# GPS.net
KiCad netlist of a schematic drawn in Altium Designer
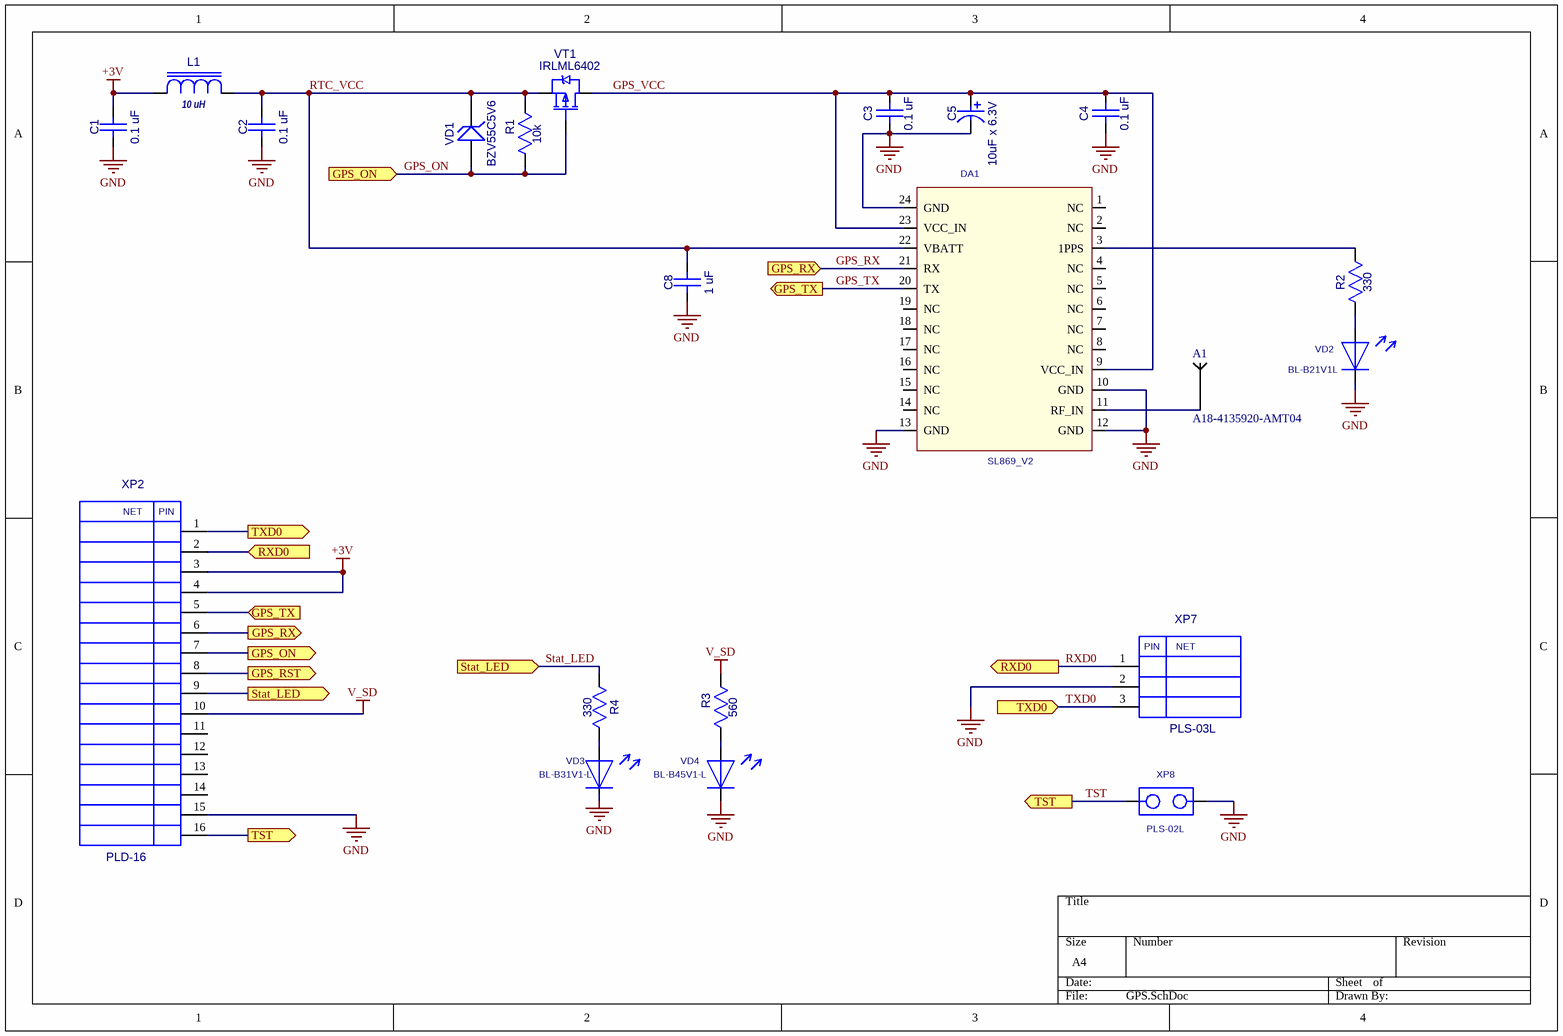
[diagram p0: GPS.SchDoc]

(export (version "E")
  (design (tool "Eeschema 10.0.6"))
  (components
    (comp (ref "A1")
      (value "A18-4135920-AMT04")
      (footprint "BY-GPS-204")
      (description "Passive GPS Antenna")
      (libsource (lib "gprs_modem_2") (part "BY-GPS-204"))
    )
    (comp (ref "C1")
      (value "0.1 uF")
      (footprint "CC0603-3M")
      (description "CC0603")
      (libsource (lib "*") (part "CC0603"))
    )
    (comp (ref "C2")
      (value "0.1 uF")
      (footprint "CC0603-3M")
      (description "CC0603")
      (libsource (lib "*") (part "CC0603"))
    )
    (comp (ref "C3")
      (value "0.1 uF")
      (footprint "CC0603-3M")
      (description "CC0603")
      (libsource (lib "*") (part "CC0603"))
    )
    (comp (ref "C4")
      (value "0.1 uF")
      (footprint "CC0603-3M")
      (description "CC0603")
      (libsource (lib "*") (part "CC0603"))
    )
    (comp (ref "C5")
      (value "10uF x 6.3V")
      (footprint "TAJ-A_M")
      (description "TAJ-A")
      (libsource (lib "gprs_modem") (part "TAJ-A"))
    )
    (comp (ref "C8")
      (value "1 uF")
      (footprint "CC0603-3M")
      (description "CC0603")
      (libsource (lib "*") (part "CC0603"))
    )
    (comp (ref "DA1") (value "SL869_V2") (footprint "SL868") (libsource (lib "gprs_modem") (part "SL869_V2")))
    (comp (ref "L1")
      (value "10 uH")
      (footprint "RC0805-MIDI-2")
      (description "L0805")
      (libsource (lib "*") (part "L0805"))
    )
    (comp (ref "R1")
      (value "10k")
      (footprint "RC0603-3M")
      (description "RC0603")
      (libsource (lib "*") (part "RC0603"))
    )
    (comp (ref "R2")
      (value "330")
      (footprint "RC0603-3M")
      (description "RC0603")
      (libsource (lib "*") (part "RC0603"))
    )
    (comp (ref "R3")
      (value "560")
      (footprint "RC0603-3M")
      (description "RC0603")
      (libsource (lib "*") (part "RC0603"))
    )
    (comp (ref "R4")
      (value "330")
      (footprint "RC0603-3M")
      (description "RC0603")
      (libsource (lib "*") (part "RC0603"))
    )
    (comp (ref "VD1")
      (value "BZV55C5V6")
      (footprint "SOD80")
      (description "Zener Voltage Regulator Diode")
      (libsource (lib "gprs_modem") (part "BZV55C5V1"))
    )
    (comp (ref "VD2")
      (value "BL-B21V1L")
      (footprint "LED3")
      (description "LED_3")
      (libsource (lib "gprs_modem") (part "LED_3"))
    )
    (comp (ref "VD3")
      (value "BL-B31V1-L")
      (footprint "LED3")
      (description "LED_3")
      (libsource (lib "gprs_modem") (part "LED_3"))
    )
    (comp (ref "VD4")
      (value "BL-B45V1-L")
      (footprint "LED3")
      (description "LED_3")
      (libsource (lib "gprs_modem") (part "LED_3"))
    )
    (comp (ref "VT1")
      (value "IRLML6402")
      (footprint "SOT-23(123)")
      (description "HEXFET Power MOSFET")
      (libsource (lib "gprs_modem") (part "IRLML6402"))
    )
    (comp (ref "XP2") (value "PLD-16") (footprint "PIN16") (libsource (lib "gprs_modem") (part "PLD-16")))
    (comp (ref "XP7") (value "PLS-03L") (footprint "PLS-03L") (libsource (lib "gprs_modem") (part "PLS-03L")))
    (comp (ref "XP8") (value "PLS-02L") (footprint "PLS-02L") (libsource (lib "gprs_modem") (part "PLS-02L")))
  )
  (nets
    (net (code "1") (name "+3V") (class "Default")
      (node (ref "C1") (pin "2") (pinfunction "B_2") (pintype "passive"))
      (node (ref "L1") (pin "1") (pinfunction "A_1") (pintype "passive"))
      (node (ref "XP2") (pin "3") (pinfunction "3_3") (pintype "passive"))
      (node (ref "XP2") (pin "4") (pinfunction "4_4") (pintype "passive"))
    )
    (net (code "2") (name "/GPS_ON") (class "Default")
      (node (ref "R1") (pin "2") (pinfunction "B_2") (pintype "passive"))
      (node (ref "VD1") (pin "1") (pinfunction "A_1") (pintype "passive"))
      (node (ref "VT1") (pin "1") (pinfunction "G_1") (pintype "passive"))
      (node (ref "XP2") (pin "7") (pinfunction "7_7") (pintype "passive"))
    )
    (net (code "3") (name "/GPS_RST") (class "Default")
      (node (ref "XP2") (pin "8") (pinfunction "8_8") (pintype "passive"))
    )
    (net (code "4") (name "/GPS_RX") (class "Default")
      (node (ref "DA1") (pin "21") (pinfunction "RX_21") (pintype "passive"))
      (node (ref "XP2") (pin "6") (pinfunction "6_6") (pintype "passive"))
    )
    (net (code "5") (name "/GPS_TX") (class "Default")
      (node (ref "DA1") (pin "20") (pinfunction "TX_20") (pintype "passive"))
      (node (ref "XP2") (pin "5") (pinfunction "5_5") (pintype "passive"))
    )
    (net (code "6") (name "/GPS_VCC") (class "Default")
      (node (ref "C3") (pin "1") (pinfunction "A_1") (pintype "passive"))
      (node (ref "C4") (pin "1") (pinfunction "A_1") (pintype "passive"))
      (node (ref "C5") (pin "1") (pinfunction "A_1") (pintype "passive"))
      (node (ref "DA1") (pin "23") (pinfunction "VCC_IN_23") (pintype "passive"))
      (node (ref "DA1") (pin "9") (pinfunction "VCC_IN_9") (pintype "passive"))
      (node (ref "VT1") (pin "3") (pinfunction "D_3") (pintype "passive"))
    )
    (net (code "7") (name "/RTC_VCC") (class "Default")
      (node (ref "C2") (pin "2") (pinfunction "B_2") (pintype "passive"))
      (node (ref "C8") (pin "2") (pinfunction "B_2") (pintype "passive"))
      (node (ref "DA1") (pin "22") (pinfunction "VBATT_22") (pintype "passive"))
      (node (ref "L1") (pin "2") (pinfunction "B_2") (pintype "passive"))
      (node (ref "R1") (pin "1") (pinfunction "A_1") (pintype "passive"))
      (node (ref "VD1") (pin "2") (pintype "passive"))
      (node (ref "VT1") (pin "2") (pinfunction "S_2") (pintype "passive"))
    )
    (net (code "8") (name "/RXD0") (class "Default")
      (node (ref "XP2") (pin "2") (pinfunction "2_2") (pintype "passive"))
      (node (ref "XP7") (pin "1") (pinfunction "1_1") (pintype "passive"))
    )
    (net (code "9") (name "/Stat_LED") (class "Default")
      (node (ref "R4") (pin "2") (pinfunction "B_2") (pintype "passive"))
      (node (ref "XP2") (pin "9") (pinfunction "9_9") (pintype "passive"))
    )
    (net (code "10") (name "/TST") (class "Default")
      (node (ref "XP2") (pin "16") (pinfunction "16_16") (pintype "passive"))
      (node (ref "XP8") (pin "1") (pintype "passive"))
    )
    (net (code "11") (name "/TXD0") (class "Default")
      (node (ref "XP2") (pin "1") (pinfunction "1_1") (pintype "passive"))
      (node (ref "XP7") (pin "3") (pinfunction "3_3") (pintype "passive"))
    )
    (net (code "12") (name "GND") (class "Default")
      (node (ref "C1") (pin "1") (pinfunction "A_1") (pintype "passive"))
      (node (ref "C2") (pin "1") (pinfunction "A_1") (pintype "passive"))
      (node (ref "C3") (pin "2") (pinfunction "B_2") (pintype "passive"))
      (node (ref "C4") (pin "2") (pinfunction "B_2") (pintype "passive"))
      (node (ref "C5") (pin "2") (pinfunction "B_2") (pintype "passive"))
      (node (ref "C8") (pin "1") (pinfunction "A_1") (pintype "passive"))
      (node (ref "DA1") (pin "10") (pinfunction "GND_10") (pintype "passive"))
      (node (ref "DA1") (pin "12") (pinfunction "GND_12") (pintype "passive"))
      (node (ref "DA1") (pin "13") (pinfunction "GND_13") (pintype "passive"))
      (node (ref "DA1") (pin "24") (pinfunction "GND_24") (pintype "passive"))
      (node (ref "VD2") (pin "1") (pintype "passive"))
      (node (ref "VD3") (pin "1") (pintype "passive"))
      (node (ref "VD4") (pin "1") (pintype "passive"))
      (node (ref "XP2") (pin "15") (pinfunction "15_15") (pintype "passive"))
      (node (ref "XP7") (pin "2") (pinfunction "2_2") (pintype "passive"))
      (node (ref "XP8") (pin "2") (pintype "passive"))
    )
    (net (code "13") (name "Net-(DA1-1PPS)") (class "Default")
      (node (ref "DA1") (pin "3") (pinfunction "1PPS_3") (pintype "passive"))
      (node (ref "R2") (pin "1") (pinfunction "A_1") (pintype "passive"))
    )
    (net (code "14") (name "Net-(DA1-RF_IN)") (class "Default")
      (node (ref "A1") (pin "1") (pinfunction "1_1") (pintype "passive"))
      (node (ref "DA1") (pin "11") (pinfunction "RF_IN_11") (pintype "passive"))
    )
    (net (code "15") (name "Net-(R2-B)") (class "Default")
      (node (ref "R2") (pin "2") (pinfunction "B_2") (pintype "passive"))
      (node (ref "VD2") (pin "2") (pintype "passive"))
    )
    (net (code "16") (name "Net-(R3-A)") (class "Default")
      (node (ref "R3") (pin "1") (pinfunction "A_1") (pintype "passive"))
      (node (ref "VD4") (pin "2") (pintype "passive"))
    )
    (net (code "17") (name "Net-(R4-A)") (class "Default")
      (node (ref "R4") (pin "1") (pinfunction "A_1") (pintype "passive"))
      (node (ref "VD3") (pin "2") (pintype "passive"))
    )
    (net (code "18") (name "V_SD") (class "Default")
      (node (ref "R3") (pin "2") (pinfunction "B_2") (pintype "passive"))
      (node (ref "XP2") (pin "10") (pinfunction "10_10") (pintype "passive"))
    )
    (net (code "19") (name "unconnected-(DA1-NC-Pad1)") (class "Default")
      (node (ref "DA1") (pin "1") (pinfunction "NC_1") (pintype "passive"))
    )
    (net (code "20") (name "unconnected-(DA1-NC-Pad2)") (class "Default")
      (node (ref "DA1") (pin "2") (pinfunction "NC_2") (pintype "passive"))
    )
    (net (code "21") (name "unconnected-(DA1-NC-Pad4)") (class "Default")
      (node (ref "DA1") (pin "4") (pinfunction "NC_4") (pintype "passive"))
    )
    (net (code "22") (name "unconnected-(DA1-NC-Pad5)") (class "Default")
      (node (ref "DA1") (pin "5") (pinfunction "NC_5") (pintype "passive"))
    )
    (net (code "23") (name "unconnected-(DA1-NC-Pad6)") (class "Default")
      (node (ref "DA1") (pin "6") (pinfunction "NC_6") (pintype "passive"))
    )
    (net (code "24") (name "unconnected-(DA1-NC-Pad7)") (class "Default")
      (node (ref "DA1") (pin "7") (pinfunction "NC_7") (pintype "passive"))
    )
    (net (code "25") (name "unconnected-(DA1-NC-Pad8)") (class "Default")
      (node (ref "DA1") (pin "8") (pinfunction "NC_8") (pintype "passive"))
    )
    (net (code "26") (name "unconnected-(DA1-NC-Pad14)") (class "Default")
      (node (ref "DA1") (pin "14") (pinfunction "NC_14") (pintype "passive"))
    )
    (net (code "27") (name "unconnected-(DA1-NC-Pad15)") (class "Default")
      (node (ref "DA1") (pin "15") (pinfunction "NC_15") (pintype "passive"))
    )
    (net (code "28") (name "unconnected-(DA1-NC-Pad16)") (class "Default")
      (node (ref "DA1") (pin "16") (pinfunction "NC_16") (pintype "passive"))
    )
    (net (code "29") (name "unconnected-(DA1-NC-Pad17)") (class "Default")
      (node (ref "DA1") (pin "17") (pinfunction "NC_17") (pintype "passive"))
    )
    (net (code "30") (name "unconnected-(DA1-NC-Pad18)") (class "Default")
      (node (ref "DA1") (pin "18") (pinfunction "NC_18") (pintype "passive"))
    )
    (net (code "31") (name "unconnected-(DA1-NC-Pad19)") (class "Default")
      (node (ref "DA1") (pin "19") (pinfunction "NC_19") (pintype "passive"))
    )
    (net (code "32") (name "unconnected-(XP2-Pad11)") (class "Default")
      (node (ref "XP2") (pin "11") (pinfunction "11_11") (pintype "passive"))
    )
    (net (code "33") (name "unconnected-(XP2-Pad12)") (class "Default")
      (node (ref "XP2") (pin "12") (pinfunction "12_12") (pintype "passive"))
    )
    (net (code "34") (name "unconnected-(XP2-Pad13)") (class "Default")
      (node (ref "XP2") (pin "13") (pinfunction "13_13") (pintype "passive"))
    )
    (net (code "35") (name "unconnected-(XP2-Pad14)") (class "Default")
      (node (ref "XP2") (pin "14") (pinfunction "14_14") (pintype "passive"))
    )
  )
)
